# LED_v2.net
KiCad netlist of a schematic drawn in Altium Designer
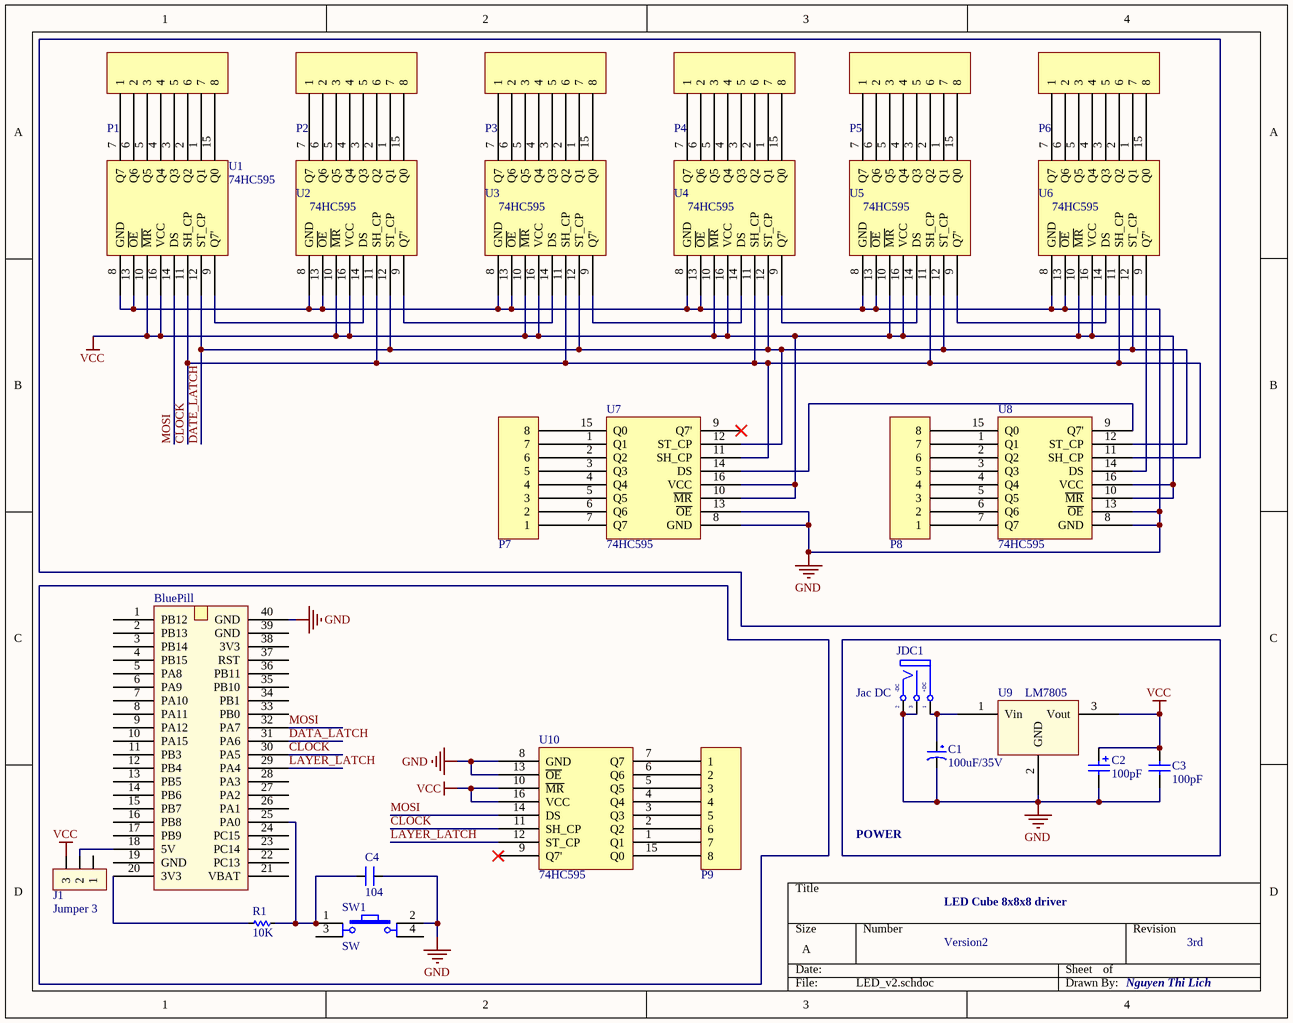
[diagram p0: LED_v2.schdoc]

(export (version "E")
  (design (tool "Eeschema 10.0.6"))
  (components
    (comp (ref "BluePill")
      (value "BluePill")
      (footprint "BluePill")
      (description "stm32f103c8t6")
      (libsource (lib "HN_Library") (part "BluePill_stm32"))
    )
    (comp (ref "C1")
      (value "100uF/35V")
      (footprint "CP1.5/3.4")
      (description "Cap 100uF/35V - 470uF/16V")
      (libsource (lib "syhaunguyen") (part "CP3"))
    )
    (comp (ref "C2")
      (value "100pF")
      (footprint "CAP ALU SIZE B")
      (description "Polarized Capacitor (Radial)")
      (fields (field (name "Comment") "Cap Pol SMD"))
      (libsource (lib "PIF_Library") (part "Cap Pol SMD"))
    )
    (comp (ref "C3")
      (value "100pF")
      (footprint "CAP-SM-0805")
      (description "Capacitor")
      (fields (field (name "Comment") "Cap Non-Pol SMD"))
      (libsource (lib "PIF_Library") (part "Cap Non-Pol SMD"))
    )
    (comp (ref "C4")
      (value "104")
      (footprint "SM-0805")
      (description "Cap SMD")
      (libsource (lib "syhaunguyen") (part "CM"))
    )
    (comp (ref "J1") (value "Jumper 3") (footprint "JP3") (libsource (lib "syhaunguyen") (part "JP3")))
    (comp (ref "JDC1")
      (value "Jac DC")
      (footprint "DC0")
      (description "Jac DC input")
      (libsource (lib "HN_Library") (part "DCIN"))
    )
    (comp (ref "P1")
      (value "Header 8")
      (footprint "JP8")
      (description "Header, 8-Pin")
      (fields (field (name "PUBLISHER") "Altium Limited"))
      (libsource (lib "PIF_Library") (part "Header 8"))
    )
    (comp (ref "P2")
      (value "Header 8")
      (footprint "JP8")
      (description "Header, 8-Pin")
      (fields (field (name "PUBLISHER") "Altium Limited"))
      (libsource (lib "PIF_Library") (part "Header 8"))
    )
    (comp (ref "P3")
      (value "Header 8")
      (footprint "JP8")
      (description "Header, 8-Pin")
      (fields (field (name "PUBLISHER") "Altium Limited"))
      (libsource (lib "PIF_Library") (part "Header 8"))
    )
    (comp (ref "P4")
      (value "Header 8")
      (footprint "JP8")
      (description "Header, 8-Pin")
      (fields (field (name "PUBLISHER") "Altium Limited"))
      (libsource (lib "PIF_Library") (part "Header 8"))
    )
    (comp (ref "P5")
      (value "Header 8")
      (footprint "JP8")
      (description "Header, 8-Pin")
      (fields (field (name "PUBLISHER") "Altium Limited"))
      (libsource (lib "PIF_Library") (part "Header 8"))
    )
    (comp (ref "P6")
      (value "Header 8")
      (footprint "JP8")
      (description "Header, 8-Pin")
      (fields (field (name "PUBLISHER") "Altium Limited"))
      (libsource (lib "PIF_Library") (part "Header 8"))
    )
    (comp (ref "P7")
      (value "Header 8")
      (footprint "JP8")
      (description "Header, 8-Pin")
      (fields (field (name "PUBLISHER") "Altium Limited"))
      (libsource (lib "") (part "Header 8_1"))
    )
    (comp (ref "P8")
      (value "Header 8")
      (footprint "JP8")
      (description "Header, 8-Pin")
      (fields (field (name "PUBLISHER") "Altium Limited"))
      (libsource (lib "") (part "Header 8_1"))
    )
    (comp (ref "P9")
      (value "Header 8")
      (footprint "JP8")
      (description "Header, 8-Pin")
      (fields (field (name "PUBLISHER") "Altium Limited"))
      (libsource (lib "") (part "Header 8_2"))
    )
    (comp (ref "R1")
      (value "10K")
      (footprint "RES-SMD-0805")
      (description "Resistor")
      (fields
        (field (name "MANUFACTURER") "Generic Components")
        (field (name "PUBLISHER") "Altium Hobart Technology Centre")
      )
      (libsource (lib "LIBRARY_FULL") (part "Res-SMD"))
    )
    (comp (ref "SW1")
      (value "SW")
      (footprint "SW4")
      (description "Switch button 4 pin")
      (libsource (lib "syhaunguyen") (part "SW4"))
    )
    (comp (ref "U1") (value "74HC595") (footprint "so16") (libsource (lib "HN_Library") (part "74HC595")))
    (comp (ref "U2") (value "74HC595") (footprint "so16") (libsource (lib "HN_Library") (part "74HC595")))
    (comp (ref "U3") (value "74HC595") (footprint "so16") (libsource (lib "HN_Library") (part "74HC595")))
    (comp (ref "U4") (value "74HC595") (footprint "so16") (libsource (lib "HN_Library") (part "74HC595")))
    (comp (ref "U5") (value "74HC595") (footprint "so16") (libsource (lib "HN_Library") (part "74HC595")))
    (comp (ref "U6") (value "74HC595") (footprint "so16") (libsource (lib "HN_Library") (part "74HC595")))
    (comp (ref "U7") (value "74HC595") (footprint "so16") (libsource (lib "") (part "74HC595_1")))
    (comp (ref "U8") (value "74HC595") (footprint "so16") (libsource (lib "") (part "74HC595_1")))
    (comp (ref "U9") (value "LM7805") (footprint "TO252-123") (libsource (lib "HN_Library") (part "LM78xx")))
    (comp (ref "U10") (value "74HC595") (footprint "so16") (libsource (lib "") (part "74HC595_2")))
  )
  (nets
    (net (code "1") (name "/CLOCK") (class "Default")
      (node (ref "BluePill") (pin "30") (pinfunction "PA5_30") (pintype "passive"))
      (node (ref "U1") (pin "11") (pinfunction "SH_CP_11") (pintype "passive"))
      (node (ref "U10") (pin "11") (pinfunction "SH_CP_11") (pintype "passive"))
      (node (ref "U2") (pin "11") (pinfunction "SH_CP_11") (pintype "passive"))
      (node (ref "U3") (pin "11") (pinfunction "SH_CP_11") (pintype "passive"))
      (node (ref "U4") (pin "11") (pinfunction "SH_CP_11") (pintype "passive"))
      (node (ref "U5") (pin "11") (pinfunction "SH_CP_11") (pintype "passive"))
      (node (ref "U6") (pin "11") (pinfunction "SH_CP_11") (pintype "passive"))
      (node (ref "U7") (pin "11") (pinfunction "SH_CP_11") (pintype "passive"))
      (node (ref "U8") (pin "11") (pinfunction "SH_CP_11") (pintype "passive"))
    )
    (net (code "2") (name "/DATA_LATCH") (class "Default")
      (node (ref "BluePill") (pin "31") (pinfunction "PA6_31") (pintype "passive"))
    )
    (net (code "3") (name "/DATE_LATCH") (class "Default")
      (node (ref "U1") (pin "12") (pinfunction "ST_CP_12") (pintype "passive"))
      (node (ref "U2") (pin "12") (pinfunction "ST_CP_12") (pintype "passive"))
      (node (ref "U3") (pin "12") (pinfunction "ST_CP_12") (pintype "passive"))
      (node (ref "U4") (pin "12") (pinfunction "ST_CP_12") (pintype "passive"))
      (node (ref "U5") (pin "12") (pinfunction "ST_CP_12") (pintype "passive"))
      (node (ref "U6") (pin "12") (pinfunction "ST_CP_12") (pintype "passive"))
      (node (ref "U7") (pin "12") (pinfunction "ST_CP_12") (pintype "passive"))
      (node (ref "U8") (pin "12") (pinfunction "ST_CP_12") (pintype "passive"))
    )
    (net (code "4") (name "/LAYER_LATCH") (class "Default")
      (node (ref "BluePill") (pin "29") (pinfunction "PA4_29") (pintype "passive"))
      (node (ref "U10") (pin "12") (pinfunction "ST_CP_12") (pintype "passive"))
    )
    (net (code "5") (name "/MOSI") (class "Default")
      (node (ref "BluePill") (pin "32") (pinfunction "PA7_32") (pintype "passive"))
      (node (ref "U1") (pin "14") (pinfunction "DS_14") (pintype "passive"))
      (node (ref "U10") (pin "14") (pinfunction "DS_14") (pintype "passive"))
    )
    (net (code "6") (name "GND") (class "Default")
      (node (ref "BluePill") (pin "40") (pinfunction "GND_40") (pintype "passive"))
      (node (ref "C1") (pin "2") (pinfunction "2_2") (pintype "passive"))
      (node (ref "C2") (pin "2") (pinfunction "2_2") (pintype "passive"))
      (node (ref "C3") (pin "1") (pinfunction "1_1") (pintype "passive"))
      (node (ref "C4") (pin "2") (pinfunction "2_2") (pintype "passive"))
      (node (ref "JDC1") (pin "2") (pinfunction "TN_2") (pintype "passive"))
      (node (ref "JDC1") (pin "3") (pinfunction "S_3") (pintype "power_in"))
      (node (ref "SW1") (pin "2") (pintype "passive"))
      (node (ref "U1") (pin "13") (pinfunction "~{OE}_13") (pintype "passive"))
      (node (ref "U1") (pin "8") (pinfunction "GND_8") (pintype "passive"))
      (node (ref "U10") (pin "13") (pinfunction "~{OE}_13") (pintype "passive"))
      (node (ref "U10") (pin "8") (pinfunction "GND_8") (pintype "passive"))
      (node (ref "U2") (pin "13") (pinfunction "~{OE}_13") (pintype "passive"))
      (node (ref "U2") (pin "8") (pinfunction "GND_8") (pintype "passive"))
      (node (ref "U3") (pin "13") (pinfunction "~{OE}_13") (pintype "passive"))
      (node (ref "U3") (pin "8") (pinfunction "GND_8") (pintype "passive"))
      (node (ref "U4") (pin "13") (pinfunction "~{OE}_13") (pintype "passive"))
      (node (ref "U4") (pin "8") (pinfunction "GND_8") (pintype "passive"))
      (node (ref "U5") (pin "13") (pinfunction "~{OE}_13") (pintype "passive"))
      (node (ref "U5") (pin "8") (pinfunction "GND_8") (pintype "passive"))
      (node (ref "U6") (pin "13") (pinfunction "~{OE}_13") (pintype "passive"))
      (node (ref "U6") (pin "8") (pinfunction "GND_8") (pintype "passive"))
      (node (ref "U7") (pin "13") (pinfunction "~{OE}_13") (pintype "passive"))
      (node (ref "U7") (pin "8") (pinfunction "GND_8") (pintype "passive"))
      (node (ref "U8") (pin "13") (pinfunction "~{OE}_13") (pintype "passive"))
      (node (ref "U8") (pin "8") (pinfunction "GND_8") (pintype "passive"))
      (node (ref "U9") (pin "2") (pinfunction "GND_2") (pintype "passive"))
    )
    (net (code "7") (name "Net-(BluePill-3V3-Pad20)") (class "Default")
      (node (ref "BluePill") (pin "20") (pinfunction "3V3_20") (pintype "passive"))
      (node (ref "R1") (pin "2") (pinfunction "2_2") (pintype "passive"))
    )
    (net (code "8") (name "Net-(BluePill-5V)") (class "Default")
      (node (ref "BluePill") (pin "18") (pinfunction "5V_18") (pintype "passive"))
      (node (ref "J1") (pin "2") (pinfunction "2_2") (pintype "passive"))
    )
    (net (code "9") (name "Net-(BluePill-PA0)") (class "Default")
      (node (ref "BluePill") (pin "25") (pinfunction "PA0_25") (pintype "passive"))
      (node (ref "C4") (pin "1") (pinfunction "1_1") (pintype "passive"))
      (node (ref "R1") (pin "1") (pinfunction "1_1") (pintype "passive"))
      (node (ref "SW1") (pin "1") (pintype "passive"))
    )
    (net (code "10") (name "Net-(JDC1-T)") (class "Default")
      (node (ref "C1") (pin "1") (pinfunction "1_1") (pintype "passive"))
      (node (ref "JDC1") (pin "1") (pinfunction "T_1") (pintype "passive"))
      (node (ref "U9") (pin "1") (pinfunction "Vin_1") (pintype "passive"))
    )
    (net (code "11") (name "Net-(U1-Q0)") (class "Default")
      (node (ref "P1") (pin "8") (pinfunction "8_8") (pintype "passive"))
      (node (ref "U1") (pin "15") (pinfunction "Q0_15") (pintype "passive"))
    )
    (net (code "12") (name "Net-(U1-Q1)") (class "Default")
      (node (ref "P1") (pin "7") (pinfunction "7_7") (pintype "passive"))
      (node (ref "U1") (pin "1") (pinfunction "Q1_1") (pintype "passive"))
    )
    (net (code "13") (name "Net-(U1-Q2)") (class "Default")
      (node (ref "P1") (pin "6") (pinfunction "6_6") (pintype "passive"))
      (node (ref "U1") (pin "2") (pinfunction "Q2_2") (pintype "passive"))
    )
    (net (code "14") (name "Net-(U1-Q3)") (class "Default")
      (node (ref "P1") (pin "5") (pinfunction "5_5") (pintype "passive"))
      (node (ref "U1") (pin "3") (pinfunction "Q3_3") (pintype "passive"))
    )
    (net (code "15") (name "Net-(U1-Q4)") (class "Default")
      (node (ref "P1") (pin "4") (pinfunction "4_4") (pintype "passive"))
      (node (ref "U1") (pin "4") (pinfunction "Q4_4") (pintype "passive"))
    )
    (net (code "16") (name "Net-(U1-Q5)") (class "Default")
      (node (ref "P1") (pin "3") (pinfunction "3_3") (pintype "passive"))
      (node (ref "U1") (pin "5") (pinfunction "Q5_5") (pintype "passive"))
    )
    (net (code "17") (name "Net-(U1-Q6)") (class "Default")
      (node (ref "P1") (pin "2") (pinfunction "2_2") (pintype "passive"))
      (node (ref "U1") (pin "6") (pinfunction "Q6_6") (pintype "passive"))
    )
    (net (code "18") (name "Net-(U1-Q7')") (class "Default")
      (node (ref "U1") (pin "9") (pinfunction "Q7'_9") (pintype "passive"))
      (node (ref "U2") (pin "14") (pinfunction "DS_14") (pintype "passive"))
    )
    (net (code "19") (name "Net-(U1-Q7)") (class "Default")
      (node (ref "P1") (pin "1") (pinfunction "1_1") (pintype "passive"))
      (node (ref "U1") (pin "7") (pinfunction "Q7_7") (pintype "passive"))
    )
    (net (code "20") (name "Net-(U2-Q0)") (class "Default")
      (node (ref "P2") (pin "8") (pinfunction "8_8") (pintype "passive"))
      (node (ref "U2") (pin "15") (pinfunction "Q0_15") (pintype "passive"))
    )
    (net (code "21") (name "Net-(U2-Q1)") (class "Default")
      (node (ref "P2") (pin "7") (pinfunction "7_7") (pintype "passive"))
      (node (ref "U2") (pin "1") (pinfunction "Q1_1") (pintype "passive"))
    )
    (net (code "22") (name "Net-(U2-Q2)") (class "Default")
      (node (ref "P2") (pin "6") (pinfunction "6_6") (pintype "passive"))
      (node (ref "U2") (pin "2") (pinfunction "Q2_2") (pintype "passive"))
    )
    (net (code "23") (name "Net-(U2-Q3)") (class "Default")
      (node (ref "P2") (pin "5") (pinfunction "5_5") (pintype "passive"))
      (node (ref "U2") (pin "3") (pinfunction "Q3_3") (pintype "passive"))
    )
    (net (code "24") (name "Net-(U2-Q4)") (class "Default")
      (node (ref "P2") (pin "4") (pinfunction "4_4") (pintype "passive"))
      (node (ref "U2") (pin "4") (pinfunction "Q4_4") (pintype "passive"))
    )
    (net (code "25") (name "Net-(U2-Q5)") (class "Default")
      (node (ref "P2") (pin "3") (pinfunction "3_3") (pintype "passive"))
      (node (ref "U2") (pin "5") (pinfunction "Q5_5") (pintype "passive"))
    )
    (net (code "26") (name "Net-(U2-Q6)") (class "Default")
      (node (ref "P2") (pin "2") (pinfunction "2_2") (pintype "passive"))
      (node (ref "U2") (pin "6") (pinfunction "Q6_6") (pintype "passive"))
    )
    (net (code "27") (name "Net-(U2-Q7')") (class "Default")
      (node (ref "U2") (pin "9") (pinfunction "Q7'_9") (pintype "passive"))
      (node (ref "U3") (pin "14") (pinfunction "DS_14") (pintype "passive"))
    )
    (net (code "28") (name "Net-(U2-Q7)") (class "Default")
      (node (ref "P2") (pin "1") (pinfunction "1_1") (pintype "passive"))
      (node (ref "U2") (pin "7") (pinfunction "Q7_7") (pintype "passive"))
    )
    (net (code "29") (name "Net-(U3-Q0)") (class "Default")
      (node (ref "P3") (pin "8") (pinfunction "8_8") (pintype "passive"))
      (node (ref "U3") (pin "15") (pinfunction "Q0_15") (pintype "passive"))
    )
    (net (code "30") (name "Net-(U3-Q1)") (class "Default")
      (node (ref "P3") (pin "7") (pinfunction "7_7") (pintype "passive"))
      (node (ref "U3") (pin "1") (pinfunction "Q1_1") (pintype "passive"))
    )
    (net (code "31") (name "Net-(U3-Q2)") (class "Default")
      (node (ref "P3") (pin "6") (pinfunction "6_6") (pintype "passive"))
      (node (ref "U3") (pin "2") (pinfunction "Q2_2") (pintype "passive"))
    )
    (net (code "32") (name "Net-(U3-Q3)") (class "Default")
      (node (ref "P3") (pin "5") (pinfunction "5_5") (pintype "passive"))
      (node (ref "U3") (pin "3") (pinfunction "Q3_3") (pintype "passive"))
    )
    (net (code "33") (name "Net-(U3-Q4)") (class "Default")
      (node (ref "P3") (pin "4") (pinfunction "4_4") (pintype "passive"))
      (node (ref "U3") (pin "4") (pinfunction "Q4_4") (pintype "passive"))
    )
    (net (code "34") (name "Net-(U3-Q5)") (class "Default")
      (node (ref "P3") (pin "3") (pinfunction "3_3") (pintype "passive"))
      (node (ref "U3") (pin "5") (pinfunction "Q5_5") (pintype "passive"))
    )
    (net (code "35") (name "Net-(U3-Q6)") (class "Default")
      (node (ref "P3") (pin "2") (pinfunction "2_2") (pintype "passive"))
      (node (ref "U3") (pin "6") (pinfunction "Q6_6") (pintype "passive"))
    )
    (net (code "36") (name "Net-(U3-Q7')") (class "Default")
      (node (ref "U3") (pin "9") (pinfunction "Q7'_9") (pintype "passive"))
      (node (ref "U4") (pin "14") (pinfunction "DS_14") (pintype "passive"))
    )
    (net (code "37") (name "Net-(U3-Q7)") (class "Default")
      (node (ref "P3") (pin "1") (pinfunction "1_1") (pintype "passive"))
      (node (ref "U3") (pin "7") (pinfunction "Q7_7") (pintype "passive"))
    )
    (net (code "38") (name "Net-(U4-Q0)") (class "Default")
      (node (ref "P4") (pin "8") (pinfunction "8_8") (pintype "passive"))
      (node (ref "U4") (pin "15") (pinfunction "Q0_15") (pintype "passive"))
    )
    (net (code "39") (name "Net-(U4-Q1)") (class "Default")
      (node (ref "P4") (pin "7") (pinfunction "7_7") (pintype "passive"))
      (node (ref "U4") (pin "1") (pinfunction "Q1_1") (pintype "passive"))
    )
    (net (code "40") (name "Net-(U4-Q2)") (class "Default")
      (node (ref "P4") (pin "6") (pinfunction "6_6") (pintype "passive"))
      (node (ref "U4") (pin "2") (pinfunction "Q2_2") (pintype "passive"))
    )
    (net (code "41") (name "Net-(U4-Q3)") (class "Default")
      (node (ref "P4") (pin "5") (pinfunction "5_5") (pintype "passive"))
      (node (ref "U4") (pin "3") (pinfunction "Q3_3") (pintype "passive"))
    )
    (net (code "42") (name "Net-(U4-Q4)") (class "Default")
      (node (ref "P4") (pin "4") (pinfunction "4_4") (pintype "passive"))
      (node (ref "U4") (pin "4") (pinfunction "Q4_4") (pintype "passive"))
    )
    (net (code "43") (name "Net-(U4-Q5)") (class "Default")
      (node (ref "P4") (pin "3") (pinfunction "3_3") (pintype "passive"))
      (node (ref "U4") (pin "5") (pinfunction "Q5_5") (pintype "passive"))
    )
    (net (code "44") (name "Net-(U4-Q6)") (class "Default")
      (node (ref "P4") (pin "2") (pinfunction "2_2") (pintype "passive"))
      (node (ref "U4") (pin "6") (pinfunction "Q6_6") (pintype "passive"))
    )
    (net (code "45") (name "Net-(U4-Q7')") (class "Default")
      (node (ref "U4") (pin "9") (pinfunction "Q7'_9") (pintype "passive"))
      (node (ref "U5") (pin "14") (pinfunction "DS_14") (pintype "passive"))
    )
    (net (code "46") (name "Net-(U4-Q7)") (class "Default")
      (node (ref "P4") (pin "1") (pinfunction "1_1") (pintype "passive"))
      (node (ref "U4") (pin "7") (pinfunction "Q7_7") (pintype "passive"))
    )
    (net (code "47") (name "Net-(U5-Q0)") (class "Default")
      (node (ref "P5") (pin "8") (pinfunction "8_8") (pintype "passive"))
      (node (ref "U5") (pin "15") (pinfunction "Q0_15") (pintype "passive"))
    )
    (net (code "48") (name "Net-(U5-Q1)") (class "Default")
      (node (ref "P5") (pin "7") (pinfunction "7_7") (pintype "passive"))
      (node (ref "U5") (pin "1") (pinfunction "Q1_1") (pintype "passive"))
    )
    (net (code "49") (name "Net-(U5-Q2)") (class "Default")
      (node (ref "P5") (pin "6") (pinfunction "6_6") (pintype "passive"))
      (node (ref "U5") (pin "2") (pinfunction "Q2_2") (pintype "passive"))
    )
    (net (code "50") (name "Net-(U5-Q3)") (class "Default")
      (node (ref "P5") (pin "5") (pinfunction "5_5") (pintype "passive"))
      (node (ref "U5") (pin "3") (pinfunction "Q3_3") (pintype "passive"))
    )
    (net (code "51") (name "Net-(U5-Q4)") (class "Default")
      (node (ref "P5") (pin "4") (pinfunction "4_4") (pintype "passive"))
      (node (ref "U5") (pin "4") (pinfunction "Q4_4") (pintype "passive"))
    )
    (net (code "52") (name "Net-(U5-Q5)") (class "Default")
      (node (ref "P5") (pin "3") (pinfunction "3_3") (pintype "passive"))
      (node (ref "U5") (pin "5") (pinfunction "Q5_5") (pintype "passive"))
    )
    (net (code "53") (name "Net-(U5-Q6)") (class "Default")
      (node (ref "P5") (pin "2") (pinfunction "2_2") (pintype "passive"))
      (node (ref "U5") (pin "6") (pinfunction "Q6_6") (pintype "passive"))
    )
    (net (code "54") (name "Net-(U5-Q7')") (class "Default")
      (node (ref "U5") (pin "9") (pinfunction "Q7'_9") (pintype "passive"))
      (node (ref "U6") (pin "14") (pinfunction "DS_14") (pintype "passive"))
    )
    (net (code "55") (name "Net-(U5-Q7)") (class "Default")
      (node (ref "P5") (pin "1") (pinfunction "1_1") (pintype "passive"))
      (node (ref "U5") (pin "7") (pinfunction "Q7_7") (pintype "passive"))
    )
    (net (code "56") (name "Net-(U6-Q0)") (class "Default")
      (node (ref "P6") (pin "8") (pinfunction "8_8") (pintype "passive"))
      (node (ref "U6") (pin "15") (pinfunction "Q0_15") (pintype "passive"))
    )
    (net (code "57") (name "Net-(U6-Q1)") (class "Default")
      (node (ref "P6") (pin "7") (pinfunction "7_7") (pintype "passive"))
      (node (ref "U6") (pin "1") (pinfunction "Q1_1") (pintype "passive"))
    )
    (net (code "58") (name "Net-(U6-Q2)") (class "Default")
      (node (ref "P6") (pin "6") (pinfunction "6_6") (pintype "passive"))
      (node (ref "U6") (pin "2") (pinfunction "Q2_2") (pintype "passive"))
    )
    (net (code "59") (name "Net-(U6-Q3)") (class "Default")
      (node (ref "P6") (pin "5") (pinfunction "5_5") (pintype "passive"))
      (node (ref "U6") (pin "3") (pinfunction "Q3_3") (pintype "passive"))
    )
    (net (code "60") (name "Net-(U6-Q4)") (class "Default")
      (node (ref "P6") (pin "4") (pinfunction "4_4") (pintype "passive"))
      (node (ref "U6") (pin "4") (pinfunction "Q4_4") (pintype "passive"))
    )
    (net (code "61") (name "Net-(U6-Q5)") (class "Default")
      (node (ref "P6") (pin "3") (pinfunction "3_3") (pintype "passive"))
      (node (ref "U6") (pin "5") (pinfunction "Q5_5") (pintype "passive"))
    )
    (net (code "62") (name "Net-(U6-Q6)") (class "Default")
      (node (ref "P6") (pin "2") (pinfunction "2_2") (pintype "passive"))
      (node (ref "U6") (pin "6") (pinfunction "Q6_6") (pintype "passive"))
    )
    (net (code "63") (name "Net-(U6-Q7')") (class "Default")
      (node (ref "U6") (pin "9") (pinfunction "Q7'_9") (pintype "passive"))
      (node (ref "U8") (pin "14") (pinfunction "DS_14") (pintype "passive"))
    )
    (net (code "64") (name "Net-(U6-Q7)") (class "Default")
      (node (ref "P6") (pin "1") (pinfunction "1_1") (pintype "passive"))
      (node (ref "U6") (pin "7") (pinfunction "Q7_7") (pintype "passive"))
    )
    (net (code "65") (name "Net-(U7-DS)") (class "Default")
      (node (ref "U7") (pin "14") (pinfunction "DS_14") (pintype "passive"))
      (node (ref "U8") (pin "9") (pinfunction "Q7'_9") (pintype "passive"))
    )
    (net (code "66") (name "Net-(U7-Q0)") (class "Default")
      (node (ref "P7") (pin "8") (pinfunction "8_8") (pintype "passive"))
      (node (ref "U7") (pin "15") (pinfunction "Q0_15") (pintype "passive"))
    )
    (net (code "67") (name "Net-(U7-Q1)") (class "Default")
      (node (ref "P7") (pin "7") (pinfunction "7_7") (pintype "passive"))
      (node (ref "U7") (pin "1") (pinfunction "Q1_1") (pintype "passive"))
    )
    (net (code "68") (name "Net-(U7-Q2)") (class "Default")
      (node (ref "P7") (pin "6") (pinfunction "6_6") (pintype "passive"))
      (node (ref "U7") (pin "2") (pinfunction "Q2_2") (pintype "passive"))
    )
    (net (code "69") (name "Net-(U7-Q3)") (class "Default")
      (node (ref "P7") (pin "5") (pinfunction "5_5") (pintype "passive"))
      (node (ref "U7") (pin "3") (pinfunction "Q3_3") (pintype "passive"))
    )
    (net (code "70") (name "Net-(U7-Q4)") (class "Default")
      (node (ref "P7") (pin "4") (pinfunction "4_4") (pintype "passive"))
      (node (ref "U7") (pin "4") (pinfunction "Q4_4") (pintype "passive"))
    )
    (net (code "71") (name "Net-(U7-Q5)") (class "Default")
      (node (ref "P7") (pin "3") (pinfunction "3_3") (pintype "passive"))
      (node (ref "U7") (pin "5") (pinfunction "Q5_5") (pintype "passive"))
    )
    (net (code "72") (name "Net-(U7-Q6)") (class "Default")
      (node (ref "P7") (pin "2") (pinfunction "2_2") (pintype "passive"))
      (node (ref "U7") (pin "6") (pinfunction "Q6_6") (pintype "passive"))
    )
    (net (code "73") (name "Net-(U7-Q7)") (class "Default")
      (node (ref "P7") (pin "1") (pinfunction "1_1") (pintype "passive"))
      (node (ref "U7") (pin "7") (pinfunction "Q7_7") (pintype "passive"))
    )
    (net (code "74") (name "Net-(U8-Q0)") (class "Default")
      (node (ref "P8") (pin "8") (pinfunction "8_8") (pintype "passive"))
      (node (ref "U8") (pin "15") (pinfunction "Q0_15") (pintype "passive"))
    )
    (net (code "75") (name "Net-(U8-Q1)") (class "Default")
      (node (ref "P8") (pin "7") (pinfunction "7_7") (pintype "passive"))
      (node (ref "U8") (pin "1") (pinfunction "Q1_1") (pintype "passive"))
    )
    (net (code "76") (name "Net-(U8-Q2)") (class "Default")
      (node (ref "P8") (pin "6") (pinfunction "6_6") (pintype "passive"))
      (node (ref "U8") (pin "2") (pinfunction "Q2_2") (pintype "passive"))
    )
    (net (code "77") (name "Net-(U8-Q3)") (class "Default")
      (node (ref "P8") (pin "5") (pinfunction "5_5") (pintype "passive"))
      (node (ref "U8") (pin "3") (pinfunction "Q3_3") (pintype "passive"))
    )
    (net (code "78") (name "Net-(U8-Q4)") (class "Default")
      (node (ref "P8") (pin "4") (pinfunction "4_4") (pintype "passive"))
      (node (ref "U8") (pin "4") (pinfunction "Q4_4") (pintype "passive"))
    )
    (net (code "79") (name "Net-(U8-Q5)") (class "Default")
      (node (ref "P8") (pin "3") (pinfunction "3_3") (pintype "passive"))
      (node (ref "U8") (pin "5") (pinfunction "Q5_5") (pintype "passive"))
    )
    (net (code "80") (name "Net-(U8-Q6)") (class "Default")
      (node (ref "P8") (pin "2") (pinfunction "2_2") (pintype "passive"))
      (node (ref "U8") (pin "6") (pinfunction "Q6_6") (pintype "passive"))
    )
    (net (code "81") (name "Net-(U8-Q7)") (class "Default")
      (node (ref "P8") (pin "1") (pinfunction "1_1") (pintype "passive"))
      (node (ref "U8") (pin "7") (pinfunction "Q7_7") (pintype "passive"))
    )
    (net (code "82") (name "Net-(U10-Q0)") (class "Default")
      (node (ref "P9") (pin "8") (pinfunction "8_8") (pintype "passive"))
      (node (ref "U10") (pin "15") (pinfunction "Q0_15") (pintype "passive"))
    )
    (net (code "83") (name "Net-(U10-Q1)") (class "Default")
      (node (ref "P9") (pin "7") (pinfunction "7_7") (pintype "passive"))
      (node (ref "U10") (pin "1") (pinfunction "Q1_1") (pintype "passive"))
    )
    (net (code "84") (name "Net-(U10-Q2)") (class "Default")
      (node (ref "P9") (pin "6") (pinfunction "6_6") (pintype "passive"))
      (node (ref "U10") (pin "2") (pinfunction "Q2_2") (pintype "passive"))
    )
    (net (code "85") (name "Net-(U10-Q3)") (class "Default")
      (node (ref "P9") (pin "5") (pinfunction "5_5") (pintype "passive"))
      (node (ref "U10") (pin "3") (pinfunction "Q3_3") (pintype "passive"))
    )
    (net (code "86") (name "Net-(U10-Q4)") (class "Default")
      (node (ref "P9") (pin "4") (pinfunction "4_4") (pintype "passive"))
      (node (ref "U10") (pin "4") (pinfunction "Q4_4") (pintype "passive"))
    )
    (net (code "87") (name "Net-(U10-Q5)") (class "Default")
      (node (ref "P9") (pin "3") (pinfunction "3_3") (pintype "passive"))
      (node (ref "U10") (pin "5") (pinfunction "Q5_5") (pintype "passive"))
    )
    (net (code "88") (name "Net-(U10-Q6)") (class "Default")
      (node (ref "P9") (pin "2") (pinfunction "2_2") (pintype "passive"))
      (node (ref "U10") (pin "6") (pinfunction "Q6_6") (pintype "passive"))
    )
    (net (code "89") (name "Net-(U10-Q7)") (class "Default")
      (node (ref "P9") (pin "1") (pinfunction "1_1") (pintype "passive"))
      (node (ref "U10") (pin "7") (pinfunction "Q7_7") (pintype "passive"))
    )
    (net (code "90") (name "VCC") (class "Default")
      (node (ref "C2") (pin "1") (pinfunction "1_1") (pintype "passive"))
      (node (ref "C3") (pin "2") (pinfunction "2_2") (pintype "passive"))
      (node (ref "J1") (pin "3") (pinfunction "3_3") (pintype "passive"))
      (node (ref "U1") (pin "10") (pinfunction "~{MR}_10") (pintype "passive"))
      (node (ref "U1") (pin "16") (pinfunction "VCC_16") (pintype "passive"))
      (node (ref "U10") (pin "10") (pinfunction "~{MR}_10") (pintype "passive"))
      (node (ref "U10") (pin "16") (pinfunction "VCC_16") (pintype "passive"))
      (node (ref "U2") (pin "10") (pinfunction "~{MR}_10") (pintype "passive"))
      (node (ref "U2") (pin "16") (pinfunction "VCC_16") (pintype "passive"))
      (node (ref "U3") (pin "10") (pinfunction "~{MR}_10") (pintype "passive"))
      (node (ref "U3") (pin "16") (pinfunction "VCC_16") (pintype "passive"))
      (node (ref "U4") (pin "10") (pinfunction "~{MR}_10") (pintype "passive"))
      (node (ref "U4") (pin "16") (pinfunction "VCC_16") (pintype "passive"))
      (node (ref "U5") (pin "10") (pinfunction "~{MR}_10") (pintype "passive"))
      (node (ref "U5") (pin "16") (pinfunction "VCC_16") (pintype "passive"))
      (node (ref "U6") (pin "10") (pinfunction "~{MR}_10") (pintype "passive"))
      (node (ref "U6") (pin "16") (pinfunction "VCC_16") (pintype "passive"))
      (node (ref "U7") (pin "10") (pinfunction "~{MR}_10") (pintype "passive"))
      (node (ref "U7") (pin "16") (pinfunction "VCC_16") (pintype "passive"))
      (node (ref "U8") (pin "10") (pinfunction "~{MR}_10") (pintype "passive"))
      (node (ref "U8") (pin "16") (pinfunction "VCC_16") (pintype "passive"))
      (node (ref "U9") (pin "3") (pinfunction "Vout_3") (pintype "passive"))
    )
    (net (code "91") (name "unconnected-(BluePill-3V3-Pad38)") (class "Default")
      (node (ref "BluePill") (pin "38") (pinfunction "3V3_38") (pintype "passive"))
    )
    (net (code "92") (name "unconnected-(BluePill-GND-Pad19)") (class "Default")
      (node (ref "BluePill") (pin "19") (pinfunction "GND_19") (pintype "passive"))
    )
    (net (code "93") (name "unconnected-(BluePill-GND-Pad39)") (class "Default")
      (node (ref "BluePill") (pin "39") (pinfunction "GND_39") (pintype "passive"))
    )
    (net (code "94") (name "unconnected-(BluePill-PA1-Pad26)") (class "Default")
      (node (ref "BluePill") (pin "26") (pinfunction "PA1_26") (pintype "passive"))
    )
    (net (code "95") (name "unconnected-(BluePill-PA2-Pad27)") (class "Default")
      (node (ref "BluePill") (pin "27") (pinfunction "PA2_27") (pintype "passive"))
    )
    (net (code "96") (name "unconnected-(BluePill-PA3-Pad28)") (class "Default")
      (node (ref "BluePill") (pin "28") (pinfunction "PA3_28") (pintype "passive"))
    )
    (net (code "97") (name "unconnected-(BluePill-PA8-Pad5)") (class "Default")
      (node (ref "BluePill") (pin "5") (pinfunction "PA8_5") (pintype "passive"))
    )
    (net (code "98") (name "unconnected-(BluePill-PA9-Pad6)") (class "Default")
      (node (ref "BluePill") (pin "6") (pinfunction "PA9_6") (pintype "passive"))
    )
    (net (code "99") (name "unconnected-(BluePill-PA10-Pad7)") (class "Default")
      (node (ref "BluePill") (pin "7") (pinfunction "PA10_7") (pintype "passive"))
    )
    (net (code "100") (name "unconnected-(BluePill-PA11-Pad8)") (class "Default")
      (node (ref "BluePill") (pin "8") (pinfunction "PA11_8") (pintype "passive"))
    )
    (net (code "101") (name "unconnected-(BluePill-PA12-Pad9)") (class "Default")
      (node (ref "BluePill") (pin "9") (pinfunction "PA12_9") (pintype "passive"))
    )
    (net (code "102") (name "unconnected-(BluePill-PA15-Pad10)") (class "Default")
      (node (ref "BluePill") (pin "10") (pinfunction "PA15_10") (pintype "passive"))
    )
    (net (code "103") (name "unconnected-(BluePill-PB0-Pad33)") (class "Default")
      (node (ref "BluePill") (pin "33") (pinfunction "PB0_33") (pintype "passive"))
    )
    (net (code "104") (name "unconnected-(BluePill-PB1-Pad34)") (class "Default")
      (node (ref "BluePill") (pin "34") (pinfunction "PB1_34") (pintype "passive"))
    )
    (net (code "105") (name "unconnected-(BluePill-PB3-Pad11)") (class "Default")
      (node (ref "BluePill") (pin "11") (pinfunction "PB3_11") (pintype "passive"))
    )
    (net (code "106") (name "unconnected-(BluePill-PB4-Pad12)") (class "Default")
      (node (ref "BluePill") (pin "12") (pinfunction "PB4_12") (pintype "passive"))
    )
    (net (code "107") (name "unconnected-(BluePill-PB5-Pad13)") (class "Default")
      (node (ref "BluePill") (pin "13") (pinfunction "PB5_13") (pintype "passive"))
    )
    (net (code "108") (name "unconnected-(BluePill-PB6-Pad14)") (class "Default")
      (node (ref "BluePill") (pin "14") (pinfunction "PB6_14") (pintype "passive"))
    )
    (net (code "109") (name "unconnected-(BluePill-PB7-Pad15)") (class "Default")
      (node (ref "BluePill") (pin "15") (pinfunction "PB7_15") (pintype "passive"))
    )
    (net (code "110") (name "unconnected-(BluePill-PB8-Pad16)") (class "Default")
      (node (ref "BluePill") (pin "16") (pinfunction "PB8_16") (pintype "passive"))
    )
    (net (code "111") (name "unconnected-(BluePill-PB9-Pad17)") (class "Default")
      (node (ref "BluePill") (pin "17") (pinfunction "PB9_17") (pintype "passive"))
    )
    (net (code "112") (name "unconnected-(BluePill-PB10-Pad35)") (class "Default")
      (node (ref "BluePill") (pin "35") (pinfunction "PB10_35") (pintype "passive"))
    )
    (net (code "113") (name "unconnected-(BluePill-PB11-Pad36)") (class "Default")
      (node (ref "BluePill") (pin "36") (pinfunction "PB11_36") (pintype "passive"))
    )
    (net (code "114") (name "unconnected-(BluePill-PB12-Pad1)") (class "Default")
      (node (ref "BluePill") (pin "1") (pinfunction "PB12_1") (pintype "passive"))
    )
    (net (code "115") (name "unconnected-(BluePill-PB13-Pad2)") (class "Default")
      (node (ref "BluePill") (pin "2") (pinfunction "PB13_2") (pintype "passive"))
    )
    (net (code "116") (name "unconnected-(BluePill-PB14-Pad3)") (class "Default")
      (node (ref "BluePill") (pin "3") (pinfunction "PB14_3") (pintype "passive"))
    )
    (net (code "117") (name "unconnected-(BluePill-PB15-Pad4)") (class "Default")
      (node (ref "BluePill") (pin "4") (pinfunction "PB15_4") (pintype "passive"))
    )
    (net (code "118") (name "unconnected-(BluePill-PC13-Pad22)") (class "Default")
      (node (ref "BluePill") (pin "22") (pinfunction "PC13_22") (pintype "passive"))
    )
    (net (code "119") (name "unconnected-(BluePill-PC14-Pad23)") (class "Default")
      (node (ref "BluePill") (pin "23") (pinfunction "PC14_23") (pintype "passive"))
    )
    (net (code "120") (name "unconnected-(BluePill-PC15-Pad24)") (class "Default")
      (node (ref "BluePill") (pin "24") (pinfunction "PC15_24") (pintype "passive"))
    )
    (net (code "121") (name "unconnected-(BluePill-RST-Pad37)") (class "Default")
      (node (ref "BluePill") (pin "37") (pinfunction "RST_37") (pintype "passive"))
    )
    (net (code "122") (name "unconnected-(BluePill-VBAT-Pad21)") (class "Default")
      (node (ref "BluePill") (pin "21") (pinfunction "VBAT_21") (pintype "passive"))
    )
    (net (code "123") (name "unconnected-(J1-Pad1)") (class "Default")
      (node (ref "J1") (pin "1") (pinfunction "1_1") (pintype "passive"))
    )
    (net (code "124") (name "unconnected-(SW1-Pad3)") (class "Default")
      (node (ref "SW1") (pin "3") (pintype "passive"))
    )
    (net (code "125") (name "unconnected-(SW1-Pad4)") (class "Default")
      (node (ref "SW1") (pin "4") (pintype "passive"))
    )
    (net (code "126") (name "unconnected-(U7-Q7'-Pad9)") (class "Default")
      (node (ref "U7") (pin "9") (pinfunction "Q7'_9") (pintype "passive+no_connect"))
    )
    (net (code "127") (name "unconnected-(U10-Q7'-Pad9)") (class "Default")
      (node (ref "U10") (pin "9") (pinfunction "Q7'_9") (pintype "passive+no_connect"))
    )
  )
)
